# Pro_Micro.net
KiCad netlist of a schematic drawn in EAGLE
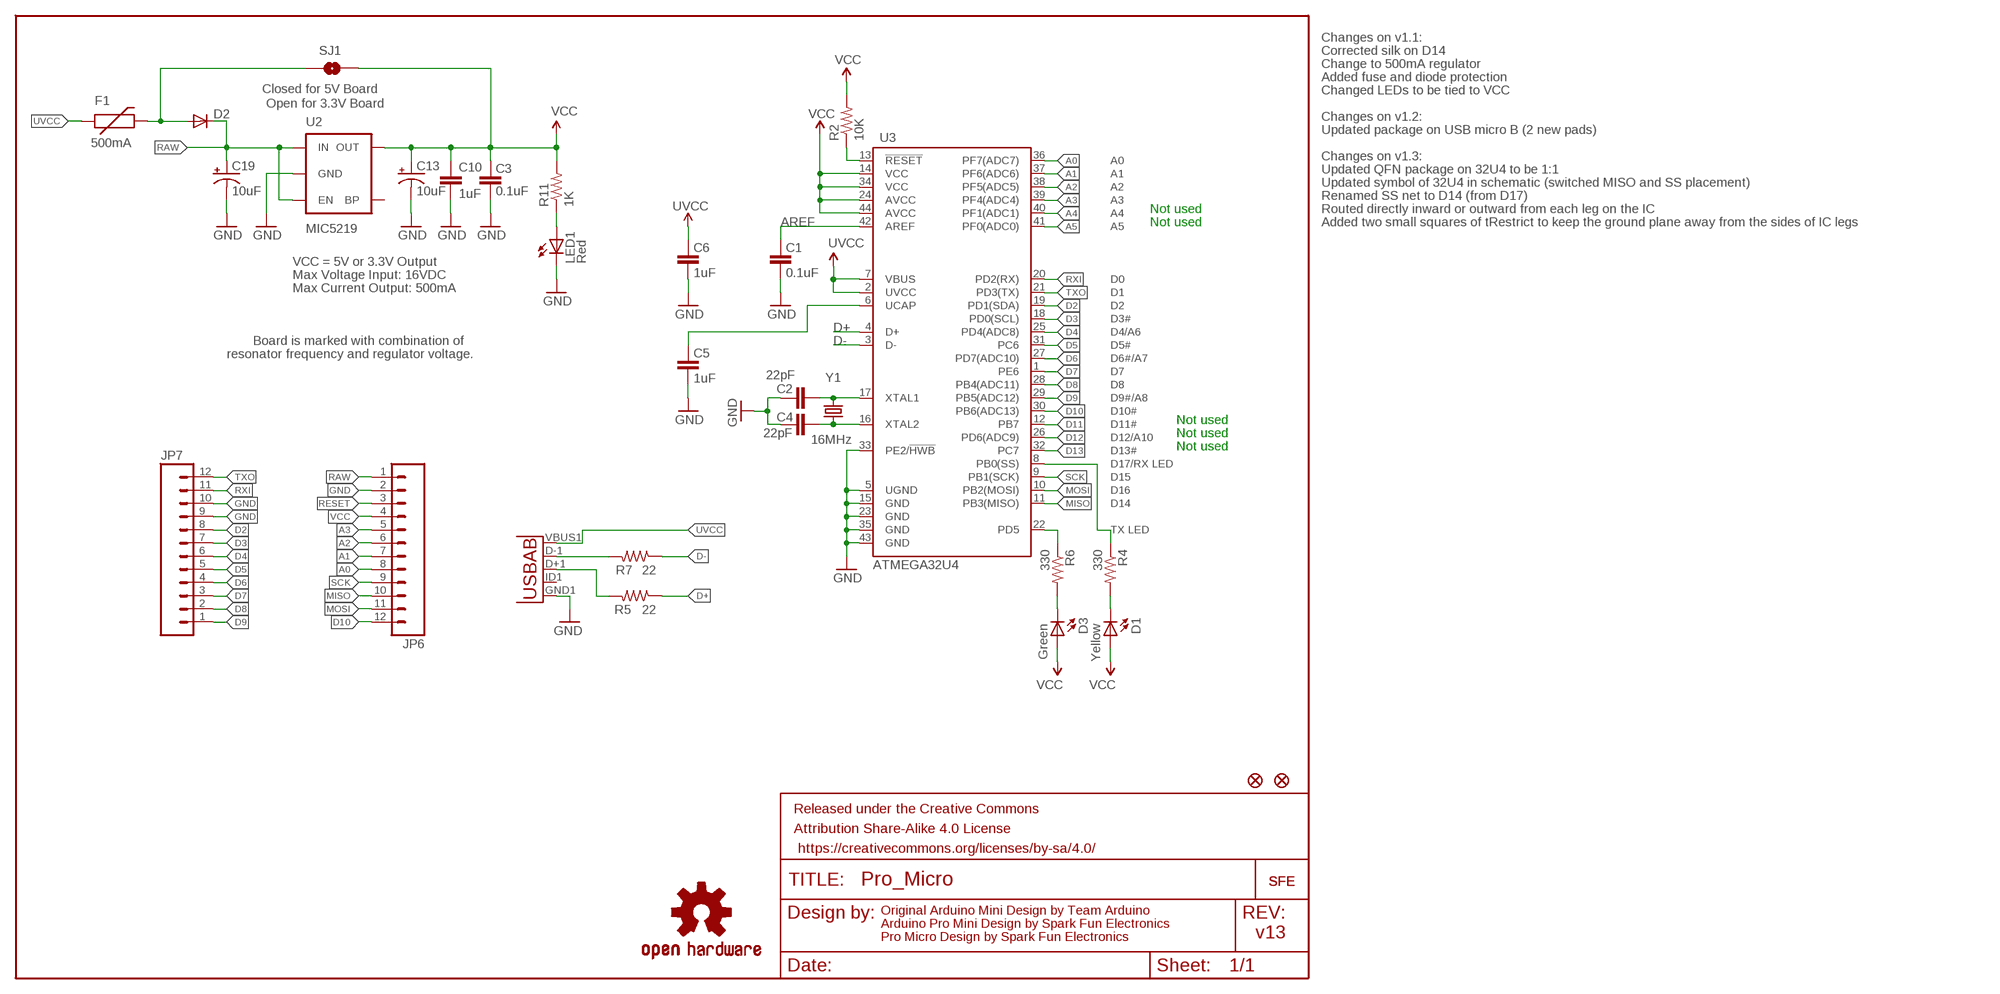
[diagram p0: schematic, sheet 1]

(export (version "E")
  (design (tool "Eeschema 10.0.6"))
  (components
    (comp (ref "C1")
      (value "0.1uF")
      (footprint "eagle-import:0603-CAP")
      (libsource (lib "eagle-import") (part "CAP0603-CAP"))
    )
    (comp (ref "C2")
      (value "22pF")
      (footprint "eagle-import:0603-CAP")
      (libsource (lib "eagle-import") (part "CAP0603-CAP"))
    )
    (comp (ref "C3")
      (value "0.1uF")
      (footprint "eagle-import:0603-CAP")
      (libsource (lib "eagle-import") (part "CAP0603-CAP"))
    )
    (comp (ref "C4")
      (value "22pF")
      (footprint "eagle-import:0603-CAP")
      (libsource (lib "eagle-import") (part "CAP0603-CAP"))
    )
    (comp (ref "C5")
      (value "1uF")
      (footprint "eagle-import:0603-CAP")
      (libsource (lib "eagle-import") (part "CAP0603-CAP"))
    )
    (comp (ref "C6")
      (value "1uF")
      (footprint "eagle-import:0603-CAP")
      (libsource (lib "eagle-import") (part "CAP0603-CAP"))
    )
    (comp (ref "C10")
      (value "1uF")
      (footprint "eagle-import:0603-CAP")
      (libsource (lib "eagle-import") (part "CAP0603-CAP"))
    )
    (comp (ref "C13")
      (value "10uF")
      (footprint "eagle-import:EIA3216")
      (libsource (lib "eagle-import") (part "CAP_POL1206"))
    )
    (comp (ref "C19")
      (value "10uF")
      (footprint "eagle-import:EIA3216")
      (libsource (lib "eagle-import") (part "CAP_POL1206"))
    )
    (comp (ref "D1")
      (value "Yellow")
      (footprint "eagle-import:LED-0603")
      (libsource (lib "eagle-import") (part "LED0603"))
    )
    (comp (ref "D2")
      (value "DIODESOD")
      (footprint "eagle-import:SOD-323")
      (libsource (lib "eagle-import") (part "DIODESOD"))
    )
    (comp (ref "D3")
      (value "Green")
      (footprint "eagle-import:LED-0603")
      (libsource (lib "eagle-import") (part "LED0603"))
    )
    (comp (ref "F1")
      (value "500mA")
      (footprint "eagle-import:PTC-1206")
      (libsource (lib "eagle-import") (part "PTCSMD"))
    )
    (comp (ref "FRAME1")
      (value "FRAME-LETTER")
      (footprint "eagle-import:CREATIVE_COMMONS")
      (libsource (lib "eagle-import") (part "FRAME-LETTER"))
    )
    (comp (ref "JP1")
      (value "FIDUCIALUFIDUCIAL")
      (footprint "eagle-import:MICRO-FIDUCIAL")
      (libsource (lib "eagle-import") (part "FIDUCIALUFIDUCIAL"))
    )
    (comp (ref "JP2")
      (value "FIDUCIALUFIDUCIAL")
      (footprint "eagle-import:MICRO-FIDUCIAL")
      (libsource (lib "eagle-import") (part "FIDUCIALUFIDUCIAL"))
    )
    (comp (ref "JP6")
      (value "M12PTH")
      (footprint "eagle-import:1X12")
      (libsource (lib "eagle-import") (part "M12PTH"))
    )
    (comp (ref "JP7")
      (value "M12PTH")
      (footprint "eagle-import:1X12")
      (libsource (lib "eagle-import") (part "M12PTH"))
    )
    (comp (ref "LED1")
      (value "Red")
      (footprint "eagle-import:LED-0603")
      (libsource (lib "eagle-import") (part "LED0603"))
    )
    (comp (ref "R2")
      (value "10K")
      (footprint "eagle-import:0603-RES")
      (libsource (lib "eagle-import") (part "RESISTOR0603-RES"))
    )
    (comp (ref "R4")
      (value "330")
      (footprint "eagle-import:0603-RES")
      (libsource (lib "eagle-import") (part "RESISTOR0603-RES"))
    )
    (comp (ref "R5")
      (value "22")
      (footprint "eagle-import:0603-RES")
      (libsource (lib "eagle-import") (part "RESISTOR0603-RES"))
    )
    (comp (ref "R6")
      (value "330")
      (footprint "eagle-import:0603-RES")
      (libsource (lib "eagle-import") (part "RESISTOR0603-RES"))
    )
    (comp (ref "R7")
      (value "22")
      (footprint "eagle-import:0603-RES")
      (libsource (lib "eagle-import") (part "RESISTOR0603-RES"))
    )
    (comp (ref "R11")
      (value "1K")
      (footprint "eagle-import:0603-RES")
      (libsource (lib "eagle-import") (part "RESISTOR0603-RES"))
    )
    (comp (ref "SJ1")
      (value "Closed for 5V Board")
      (footprint "eagle-import:SJ_2S")
      (libsource (lib "eagle-import") (part "SOLDERJUMPERNC"))
    )
    (comp (ref "U$1")
      (value "LOGO-SFESK")
      (footprint "eagle-import:SFE-LOGO-FLAME")
      (libsource (lib "eagle-import") (part "LOGO-SFESK"))
    )
    (comp (ref "U$3")
      (value "OSHW-LOGOS")
      (footprint "eagle-import:OSHW-LOGO-S")
      (libsource (lib "eagle-import") (part "OSHW-LOGOS"))
    )
    (comp (ref "U$11")
      (value "LOGO-SFENEW")
      (footprint "eagle-import:SFE-NEW-WEBLOGO")
      (libsource (lib "eagle-import") (part "LOGO-SFENEW"))
    )
    (comp (ref "U2")
      (value "MIC5219")
      (footprint "eagle-import:SOT23-5")
      (libsource (lib "eagle-import") (part "V_REG_LDOSMD"))
    )
    (comp (ref "U3")
      (value "ATMEGA32U4")
      (footprint "eagle-import:QFN-44-NOPAD_1_1-LESS_PASTE")
      (libsource (lib "eagle-import") (part "ATMEGA32U41{colon}1-LESS_PASTE"))
    )
    (comp (ref "X1")
      (value "USB-ABIN&OUT")
      (footprint "eagle-import:USB-AB-MICRO-SMD-V03-IN&OUT")
      (libsource (lib "eagle-import") (part "USB-ABIN&OUT"))
    )
    (comp (ref "Y1")
      (value "16MHz")
      (footprint "eagle-import:CRYSTAL-SMD-5X3")
      (libsource (lib "eagle-import") (part "CRYSTAL5X3"))
    )
  )
  (nets
    (net (code "1") (name "/AREF") (class "Default")
      (node (ref "C1") (pin "2") (pinfunction "2_2") (pintype "passive"))
      (node (ref "U3") (pin "42") (pinfunction "AREF_42") (pintype "bidirectional"))
    )
    (net (code "2") (name "A0") (class "Default")
      (node (ref "JP6") (pin "8") (pinfunction "8_8") (pintype "passive"))
      (node (ref "U3") (pin "36") (pinfunction "PF7(ADC7)_36") (pintype "bidirectional"))
    )
    (net (code "3") (name "A1") (class "Default")
      (node (ref "JP6") (pin "7") (pinfunction "7_7") (pintype "passive"))
      (node (ref "U3") (pin "37") (pinfunction "PF6(ADC6)_37") (pintype "bidirectional"))
    )
    (net (code "4") (name "A2") (class "Default")
      (node (ref "JP6") (pin "6") (pinfunction "6_6") (pintype "passive"))
      (node (ref "U3") (pin "38") (pinfunction "PF5(ADC5)_38") (pintype "bidirectional"))
    )
    (net (code "5") (name "A3") (class "Default")
      (node (ref "JP6") (pin "5") (pinfunction "5_5") (pintype "passive"))
      (node (ref "U3") (pin "39") (pinfunction "PF4(ADC4)_39") (pintype "bidirectional"))
    )
    (net (code "6") (name "A4") (class "Default")
      (node (ref "U3") (pin "40") (pinfunction "PF1(ADC1)_40") (pintype "bidirectional"))
    )
    (net (code "7") (name "A5") (class "Default")
      (node (ref "U3") (pin "41") (pinfunction "PF0(ADC0)_41") (pintype "bidirectional"))
    )
    (net (code "8") (name "D+") (class "Default")
      (node (ref "R5") (pin "1") (pinfunction "1_1") (pintype "passive"))
      (node (ref "U3") (pin "4") (pinfunction "D+_4") (pintype "bidirectional"))
    )
    (net (code "9") (name "D-") (class "Default")
      (node (ref "R7") (pin "1") (pinfunction "1_1") (pintype "passive"))
      (node (ref "U3") (pin "3") (pinfunction "D-_3") (pintype "bidirectional"))
    )
    (net (code "10") (name "D2") (class "Default")
      (node (ref "JP7") (pin "8") (pinfunction "8_8") (pintype "passive"))
      (node (ref "U3") (pin "19") (pinfunction "PD1(SDA)_19") (pintype "bidirectional"))
    )
    (net (code "11") (name "D3") (class "Default")
      (node (ref "JP7") (pin "7") (pinfunction "7_7") (pintype "passive"))
      (node (ref "U3") (pin "18") (pinfunction "PD0(SCL)_18") (pintype "bidirectional"))
    )
    (net (code "12") (name "D4") (class "Default")
      (node (ref "JP7") (pin "6") (pinfunction "6_6") (pintype "passive"))
      (node (ref "U3") (pin "25") (pinfunction "PD4(ADC8)_25") (pintype "bidirectional"))
    )
    (net (code "13") (name "D5") (class "Default")
      (node (ref "JP7") (pin "5") (pinfunction "5_5") (pintype "passive"))
      (node (ref "U3") (pin "31") (pinfunction "PC6_31") (pintype "bidirectional"))
    )
    (net (code "14") (name "D6") (class "Default")
      (node (ref "JP7") (pin "4") (pinfunction "4_4") (pintype "passive"))
      (node (ref "U3") (pin "27") (pinfunction "PD7(ADC10)_27") (pintype "bidirectional"))
    )
    (net (code "15") (name "D7") (class "Default")
      (node (ref "JP7") (pin "3") (pinfunction "3_3") (pintype "passive"))
      (node (ref "U3") (pin "1") (pinfunction "PE6_1") (pintype "bidirectional"))
    )
    (net (code "16") (name "D8") (class "Default")
      (node (ref "JP7") (pin "2") (pinfunction "2_2") (pintype "passive"))
      (node (ref "U3") (pin "28") (pinfunction "PB4(ADC11)_28") (pintype "bidirectional"))
    )
    (net (code "17") (name "D9") (class "Default")
      (node (ref "JP7") (pin "1") (pinfunction "1_1") (pintype "passive"))
      (node (ref "U3") (pin "29") (pinfunction "PB5(ADC12)_29") (pintype "bidirectional"))
    )
    (net (code "18") (name "D10") (class "Default")
      (node (ref "JP6") (pin "12") (pinfunction "12_12") (pintype "passive"))
      (node (ref "U3") (pin "30") (pinfunction "PB6(ADC13)_30") (pintype "bidirectional"))
    )
    (net (code "19") (name "D11") (class "Default")
      (node (ref "U3") (pin "12") (pinfunction "PB7_12") (pintype "bidirectional"))
    )
    (net (code "20") (name "D12") (class "Default")
      (node (ref "U3") (pin "26") (pinfunction "PD6(ADC9)_26") (pintype "bidirectional"))
    )
    (net (code "21") (name "D13") (class "Default")
      (node (ref "U3") (pin "32") (pinfunction "PC7_32") (pintype "bidirectional"))
    )
    (net (code "22") (name "GND") (class "Default")
      (node (ref "C1") (pin "1") (pinfunction "1_1") (pintype "passive"))
      (node (ref "C10") (pin "2") (pinfunction "2_2") (pintype "passive"))
      (node (ref "C13") (pin "C") (pinfunction "-_C") (pintype "passive"))
      (node (ref "C19") (pin "C") (pinfunction "-_C") (pintype "passive"))
      (node (ref "C2") (pin "2") (pinfunction "2_2") (pintype "passive"))
      (node (ref "C3") (pin "1") (pinfunction "1_1") (pintype "passive"))
      (node (ref "C4") (pin "2") (pinfunction "2_2") (pintype "passive"))
      (node (ref "C5") (pin "1") (pinfunction "1_1") (pintype "passive"))
      (node (ref "C6") (pin "1") (pinfunction "1_1") (pintype "passive"))
      (node (ref "JP6") (pin "2") (pinfunction "2_2") (pintype "passive"))
      (node (ref "JP7") (pin "10") (pinfunction "10_10") (pintype "passive"))
      (node (ref "JP7") (pin "9") (pinfunction "9_9") (pintype "passive"))
      (node (ref "LED1") (pin "C") (pinfunction "C_C") (pintype "passive"))
      (node (ref "U2") (pin "2") (pinfunction "GND_2") (pintype "input"))
      (node (ref "U3") (pin "15") (pinfunction "GND_15") (pintype "bidirectional"))
      (node (ref "U3") (pin "23") (pinfunction "GND_23") (pintype "bidirectional"))
      (node (ref "U3") (pin "33") (pinfunction "PE2/~{HWB}_33") (pintype "bidirectional"))
      (node (ref "U3") (pin "35") (pinfunction "GND_35") (pintype "bidirectional"))
      (node (ref "U3") (pin "43") (pinfunction "GND_43") (pintype "bidirectional"))
      (node (ref "U3") (pin "5") (pinfunction "UGND_5") (pintype "bidirectional"))
      (node (ref "X1") (pin "GND1") (pinfunction "GND_GND1") (pintype "bidirectional"))
    )
    (net (code "23") (name "MISO") (class "Default")
      (node (ref "JP6") (pin "10") (pinfunction "10_10") (pintype "passive"))
      (node (ref "U3") (pin "11") (pinfunction "PB3(MISO)_11") (pintype "bidirectional"))
    )
    (net (code "24") (name "MOSI") (class "Default")
      (node (ref "JP6") (pin "11") (pinfunction "11_11") (pintype "passive"))
      (node (ref "U3") (pin "10") (pinfunction "PB2(MOSI)_10") (pintype "bidirectional"))
    )
    (net (code "25") (name "Net-(D1-PadC)") (class "Default")
      (node (ref "D1") (pin "C") (pinfunction "C_C") (pintype "passive"))
      (node (ref "R4") (pin "2") (pinfunction "2_2") (pintype "passive"))
    )
    (net (code "26") (name "Net-(D2-A)") (class "Default")
      (node (ref "D2") (pin "2") (pinfunction "A_2") (pintype "passive"))
      (node (ref "F1") (pin "2") (pinfunction "2_2") (pintype "bidirectional"))
      (node (ref "SJ1") (pin "1") (pinfunction "1_1") (pintype "passive"))
    )
    (net (code "27") (name "Net-(D3-PadC)") (class "Default")
      (node (ref "D3") (pin "C") (pinfunction "C_C") (pintype "passive"))
      (node (ref "R6") (pin "2") (pinfunction "2_2") (pintype "passive"))
    )
    (net (code "28") (name "Net-(LED1-PadA)") (class "Default")
      (node (ref "LED1") (pin "A") (pinfunction "A_A") (pintype "passive"))
      (node (ref "R11") (pin "1") (pinfunction "1_1") (pintype "passive"))
    )
    (net (code "29") (name "Net-(U3-PB0(SS))") (class "Default")
      (node (ref "R4") (pin "1") (pinfunction "1_1") (pintype "passive"))
      (node (ref "U3") (pin "8") (pinfunction "PB0(SS)_8") (pintype "bidirectional"))
    )
    (net (code "30") (name "Net-(U3-PD5)") (class "Default")
      (node (ref "R6") (pin "1") (pinfunction "1_1") (pintype "passive"))
      (node (ref "U3") (pin "22") (pinfunction "PD5_22") (pintype "bidirectional"))
    )
    (net (code "31") (name "Net-(U3-UCAP)") (class "Default")
      (node (ref "C5") (pin "2") (pinfunction "2_2") (pintype "passive"))
      (node (ref "U3") (pin "6") (pinfunction "UCAP_6") (pintype "bidirectional"))
    )
    (net (code "32") (name "Net-(U3-XTAL1)") (class "Default")
      (node (ref "C2") (pin "1") (pinfunction "1_1") (pintype "passive"))
      (node (ref "U3") (pin "17") (pinfunction "XTAL1_17") (pintype "bidirectional"))
      (node (ref "Y1") (pin "3") (pinfunction "2_3") (pintype "passive"))
    )
    (net (code "33") (name "Net-(U3-XTAL2)") (class "Default")
      (node (ref "C4") (pin "1") (pinfunction "1_1") (pintype "passive"))
      (node (ref "U3") (pin "16") (pinfunction "XTAL2_16") (pintype "bidirectional"))
      (node (ref "Y1") (pin "1") (pinfunction "1_1") (pintype "passive"))
    )
    (net (code "34") (name "Net-(X1-D+)") (class "Default")
      (node (ref "R5") (pin "2") (pinfunction "2_2") (pintype "passive"))
      (node (ref "X1") (pin "D+1") (pinfunction "D+_D+1") (pintype "bidirectional"))
    )
    (net (code "35") (name "Net-(X1-D-)") (class "Default")
      (node (ref "R7") (pin "2") (pinfunction "2_2") (pintype "passive"))
      (node (ref "X1") (pin "D-1") (pinfunction "D-_D-1") (pintype "bidirectional"))
    )
    (net (code "36") (name "RAW") (class "Default")
      (node (ref "C19") (pin "A") (pinfunction "+_A") (pintype "passive"))
      (node (ref "D2") (pin "1") (pinfunction "C_1") (pintype "passive"))
      (node (ref "JP6") (pin "1") (pinfunction "1_1") (pintype "passive"))
      (node (ref "U2") (pin "1") (pinfunction "IN_1") (pintype "input"))
      (node (ref "U2") (pin "3") (pinfunction "EN_3") (pintype "input"))
    )
    (net (code "37") (name "RESET") (class "Default")
      (node (ref "JP6") (pin "3") (pinfunction "3_3") (pintype "passive"))
      (node (ref "R2") (pin "1") (pinfunction "1_1") (pintype "passive"))
      (node (ref "U3") (pin "13") (pinfunction "~{RESET}_13") (pintype "bidirectional"))
    )
    (net (code "38") (name "RXI") (class "Default")
      (node (ref "JP7") (pin "11") (pinfunction "11_11") (pintype "passive"))
      (node (ref "U3") (pin "20") (pinfunction "PD2(RX)_20") (pintype "bidirectional"))
    )
    (net (code "39") (name "SCK") (class "Default")
      (node (ref "JP6") (pin "9") (pinfunction "9_9") (pintype "passive"))
      (node (ref "U3") (pin "9") (pinfunction "PB1(SCK)_9") (pintype "bidirectional"))
    )
    (net (code "40") (name "TXO") (class "Default")
      (node (ref "JP7") (pin "12") (pinfunction "12_12") (pintype "passive"))
      (node (ref "U3") (pin "21") (pinfunction "PD3(TX)_21") (pintype "bidirectional"))
    )
    (net (code "41") (name "UVCC") (class "Default")
      (node (ref "C6") (pin "2") (pinfunction "2_2") (pintype "passive"))
      (node (ref "F1") (pin "1") (pinfunction "1_1") (pintype "bidirectional"))
      (node (ref "U3") (pin "2") (pinfunction "UVCC_2") (pintype "bidirectional"))
      (node (ref "U3") (pin "7") (pinfunction "VBUS_7") (pintype "bidirectional"))
      (node (ref "X1") (pin "VBUS1") (pinfunction "VBUS_VBUS1") (pintype "bidirectional"))
    )
    (net (code "42") (name "VCC") (class "Default")
      (node (ref "C10") (pin "1") (pinfunction "1_1") (pintype "passive"))
      (node (ref "C13") (pin "A") (pinfunction "+_A") (pintype "passive"))
      (node (ref "C3") (pin "2") (pinfunction "2_2") (pintype "passive"))
      (node (ref "D1") (pin "A") (pinfunction "A_A") (pintype "passive"))
      (node (ref "D3") (pin "A") (pinfunction "A_A") (pintype "passive"))
      (node (ref "JP6") (pin "4") (pinfunction "4_4") (pintype "passive"))
      (node (ref "R11") (pin "2") (pinfunction "2_2") (pintype "passive"))
      (node (ref "R2") (pin "2") (pinfunction "2_2") (pintype "passive"))
      (node (ref "SJ1") (pin "2") (pinfunction "2_2") (pintype "passive"))
      (node (ref "U2") (pin "5") (pinfunction "OUT_5") (pintype "passive"))
      (node (ref "U3") (pin "14") (pinfunction "VCC_14") (pintype "bidirectional"))
      (node (ref "U3") (pin "24") (pinfunction "AVCC_24") (pintype "bidirectional"))
      (node (ref "U3") (pin "34") (pinfunction "VCC_34") (pintype "bidirectional"))
      (node (ref "U3") (pin "44") (pinfunction "AVCC_44") (pintype "bidirectional"))
    )
    (net (code "43") (name "unconnected-(U2-BP-Pad4)") (class "Default")
      (node (ref "U2") (pin "4") (pinfunction "BP_4") (pintype "input"))
    )
    (net (code "44") (name "unconnected-(X1-USBID-PadID1)") (class "Default")
      (node (ref "X1") (pin "ID1") (pinfunction "USBID_ID1") (pintype "bidirectional"))
    )
  )
)
